# prototype.net
KiCad netlist of a schematic drawn in EAGLE
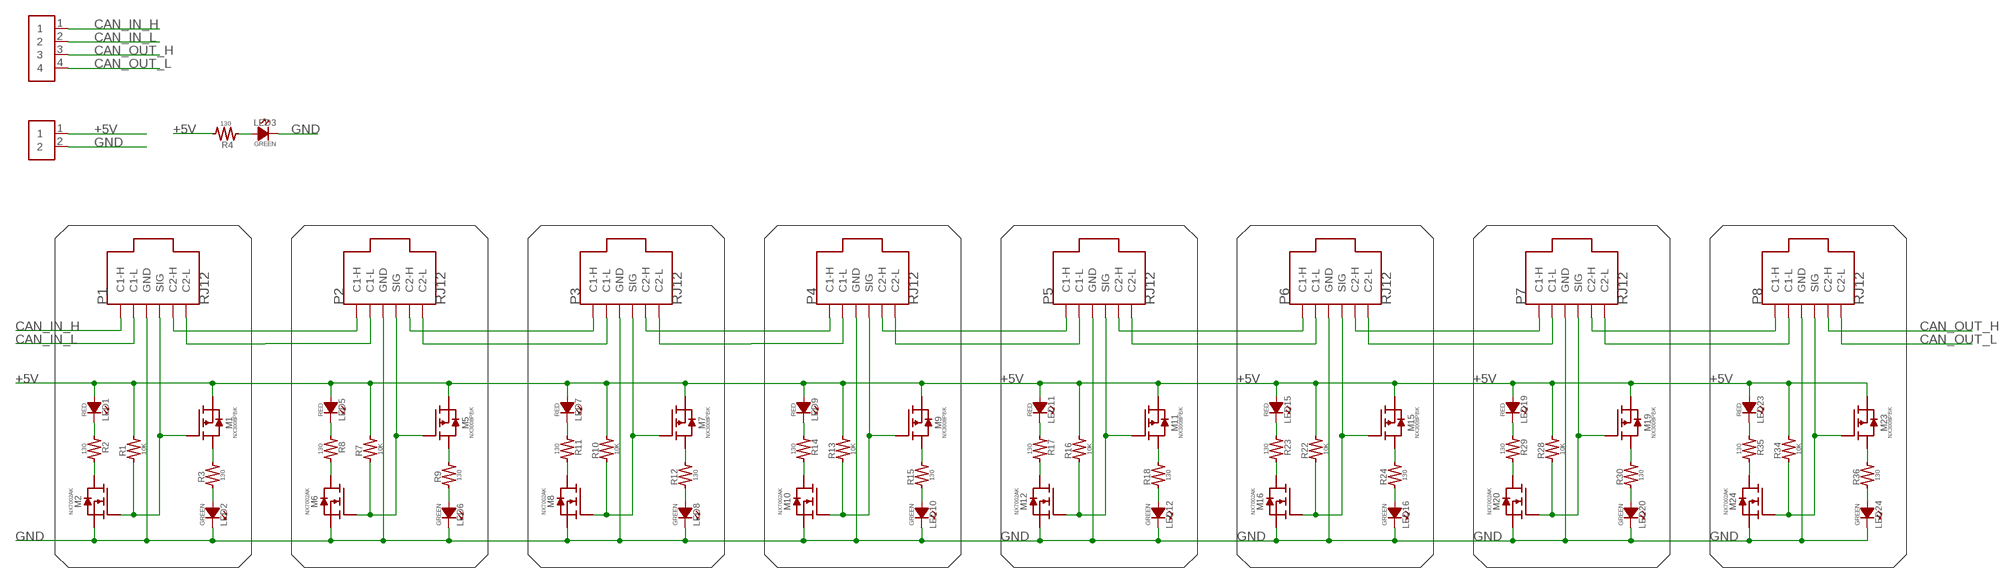
[diagram p0: schematic, sheet 1]

(export (version "E")
  (design (tool "Eeschema 10.0.6"))
  (components
    (comp (ref "LED1")
      (value "RED")
      (footprint "eagle-import:0603-LED")
      (libsource (lib "eagle-import") (part "150060RS75000"))
    )
    (comp (ref "LED2")
      (value "GREEN")
      (footprint "eagle-import:0603-LED")
      (libsource (lib "eagle-import") (part "150060VS75000"))
    )
    (comp (ref "LED3")
      (value "GREEN")
      (footprint "eagle-import:0603-LED")
      (libsource (lib "eagle-import") (part "150060VS75000"))
    )
    (comp (ref "LED5")
      (value "RED")
      (footprint "eagle-import:0603-LED")
      (libsource (lib "eagle-import") (part "150060RS75000"))
    )
    (comp (ref "LED6")
      (value "GREEN")
      (footprint "eagle-import:0603-LED")
      (libsource (lib "eagle-import") (part "150060VS75000"))
    )
    (comp (ref "LED7")
      (value "RED")
      (footprint "eagle-import:0603-LED")
      (libsource (lib "eagle-import") (part "150060RS75000"))
    )
    (comp (ref "LED8")
      (value "GREEN")
      (footprint "eagle-import:0603-LED")
      (libsource (lib "eagle-import") (part "150060VS75000"))
    )
    (comp (ref "LED9")
      (value "RED")
      (footprint "eagle-import:0603-LED")
      (libsource (lib "eagle-import") (part "150060RS75000"))
    )
    (comp (ref "LED10")
      (value "GREEN")
      (footprint "eagle-import:0603-LED")
      (libsource (lib "eagle-import") (part "150060VS75000"))
    )
    (comp (ref "LED11")
      (value "RED")
      (footprint "eagle-import:0603-LED")
      (libsource (lib "eagle-import") (part "150060RS75000"))
    )
    (comp (ref "LED12")
      (value "GREEN")
      (footprint "eagle-import:0603-LED")
      (libsource (lib "eagle-import") (part "150060VS75000"))
    )
    (comp (ref "LED15")
      (value "RED")
      (footprint "eagle-import:0603-LED")
      (libsource (lib "eagle-import") (part "150060RS75000"))
    )
    (comp (ref "LED16")
      (value "GREEN")
      (footprint "eagle-import:0603-LED")
      (libsource (lib "eagle-import") (part "150060VS75000"))
    )
    (comp (ref "LED19")
      (value "RED")
      (footprint "eagle-import:0603-LED")
      (libsource (lib "eagle-import") (part "150060RS75000"))
    )
    (comp (ref "LED20")
      (value "GREEN")
      (footprint "eagle-import:0603-LED")
      (libsource (lib "eagle-import") (part "150060VS75000"))
    )
    (comp (ref "LED23")
      (value "RED")
      (footprint "eagle-import:0603-LED")
      (libsource (lib "eagle-import") (part "150060RS75000"))
    )
    (comp (ref "LED24")
      (value "GREEN")
      (footprint "eagle-import:0603-LED")
      (libsource (lib "eagle-import") (part "150060VS75000"))
    )
    (comp (ref "M1")
      (value "NX3008PBK")
      (footprint "eagle-import:SOT23")
      (libsource (lib "eagle-import") (part "NX3008PBK"))
    )
    (comp (ref "M2")
      (value "NX7002AK")
      (footprint "eagle-import:SOT23")
      (libsource (lib "eagle-import") (part "NX7002AK"))
    )
    (comp (ref "M5")
      (value "NX3008PBK")
      (footprint "eagle-import:SOT23")
      (libsource (lib "eagle-import") (part "NX3008PBK"))
    )
    (comp (ref "M6")
      (value "NX7002AK")
      (footprint "eagle-import:SOT23")
      (libsource (lib "eagle-import") (part "NX7002AK"))
    )
    (comp (ref "M7")
      (value "NX3008PBK")
      (footprint "eagle-import:SOT23")
      (libsource (lib "eagle-import") (part "NX3008PBK"))
    )
    (comp (ref "M8")
      (value "NX7002AK")
      (footprint "eagle-import:SOT23")
      (libsource (lib "eagle-import") (part "NX7002AK"))
    )
    (comp (ref "M9")
      (value "NX3008PBK")
      (footprint "eagle-import:SOT23")
      (libsource (lib "eagle-import") (part "NX3008PBK"))
    )
    (comp (ref "M10")
      (value "NX7002AK")
      (footprint "eagle-import:SOT23")
      (libsource (lib "eagle-import") (part "NX7002AK"))
    )
    (comp (ref "M11")
      (value "NX3008PBK")
      (footprint "eagle-import:SOT23")
      (libsource (lib "eagle-import") (part "NX3008PBK"))
    )
    (comp (ref "M12")
      (value "NX7002AK")
      (footprint "eagle-import:SOT23")
      (libsource (lib "eagle-import") (part "NX7002AK"))
    )
    (comp (ref "M15")
      (value "NX3008PBK")
      (footprint "eagle-import:SOT23")
      (libsource (lib "eagle-import") (part "NX3008PBK"))
    )
    (comp (ref "M16")
      (value "NX7002AK")
      (footprint "eagle-import:SOT23")
      (libsource (lib "eagle-import") (part "NX7002AK"))
    )
    (comp (ref "M19")
      (value "NX3008PBK")
      (footprint "eagle-import:SOT23")
      (libsource (lib "eagle-import") (part "NX3008PBK"))
    )
    (comp (ref "M20")
      (value "NX7002AK")
      (footprint "eagle-import:SOT23")
      (libsource (lib "eagle-import") (part "NX7002AK"))
    )
    (comp (ref "M23")
      (value "NX3008PBK")
      (footprint "eagle-import:SOT23")
      (libsource (lib "eagle-import") (part "NX3008PBK"))
    )
    (comp (ref "M24")
      (value "NX7002AK")
      (footprint "eagle-import:SOT23")
      (libsource (lib "eagle-import") (part "NX7002AK"))
    )
    (comp (ref "P1")
      (value "RJ12")
      (footprint "eagle-import:RJ12")
      (libsource (lib "eagle-import") (part "RJ12"))
    )
    (comp (ref "P2")
      (value "RJ12")
      (footprint "eagle-import:RJ12")
      (libsource (lib "eagle-import") (part "RJ12"))
    )
    (comp (ref "P3")
      (value "RJ12")
      (footprint "eagle-import:RJ12")
      (libsource (lib "eagle-import") (part "RJ12"))
    )
    (comp (ref "P4")
      (value "RJ12")
      (footprint "eagle-import:RJ12")
      (libsource (lib "eagle-import") (part "RJ12"))
    )
    (comp (ref "P5")
      (value "RJ12")
      (footprint "eagle-import:RJ12")
      (libsource (lib "eagle-import") (part "RJ12"))
    )
    (comp (ref "P6")
      (value "RJ12")
      (footprint "eagle-import:RJ12")
      (libsource (lib "eagle-import") (part "RJ12"))
    )
    (comp (ref "P7")
      (value "RJ12")
      (footprint "eagle-import:RJ12")
      (libsource (lib "eagle-import") (part "RJ12"))
    )
    (comp (ref "P8")
      (value "RJ12")
      (footprint "eagle-import:RJ12")
      (libsource (lib "eagle-import") (part "RJ12"))
    )
    (comp (ref "R1")
      (value "10K")
      (footprint "eagle-import:0402")
      (libsource (lib "eagle-import") (part "10K0402"))
    )
    (comp (ref "R2")
      (value "130")
      (footprint "eagle-import:0402")
      (libsource (lib "eagle-import") (part "1300402"))
    )
    (comp (ref "R3")
      (value "130")
      (footprint "eagle-import:0402")
      (libsource (lib "eagle-import") (part "1300402"))
    )
    (comp (ref "R4")
      (value "130")
      (footprint "eagle-import:0402")
      (libsource (lib "eagle-import") (part "1300402"))
    )
    (comp (ref "R7")
      (value "10K")
      (footprint "eagle-import:0402")
      (libsource (lib "eagle-import") (part "10K0402"))
    )
    (comp (ref "R8")
      (value "130")
      (footprint "eagle-import:0402")
      (libsource (lib "eagle-import") (part "1300402"))
    )
    (comp (ref "R9")
      (value "130")
      (footprint "eagle-import:0402")
      (libsource (lib "eagle-import") (part "1300402"))
    )
    (comp (ref "R10")
      (value "10K")
      (footprint "eagle-import:0402")
      (libsource (lib "eagle-import") (part "10K0402"))
    )
    (comp (ref "R11")
      (value "130")
      (footprint "eagle-import:0402")
      (libsource (lib "eagle-import") (part "1300402"))
    )
    (comp (ref "R12")
      (value "130")
      (footprint "eagle-import:0402")
      (libsource (lib "eagle-import") (part "1300402"))
    )
    (comp (ref "R13")
      (value "10K")
      (footprint "eagle-import:0402")
      (libsource (lib "eagle-import") (part "10K0402"))
    )
    (comp (ref "R14")
      (value "130")
      (footprint "eagle-import:0402")
      (libsource (lib "eagle-import") (part "1300402"))
    )
    (comp (ref "R15")
      (value "130")
      (footprint "eagle-import:0402")
      (libsource (lib "eagle-import") (part "1300402"))
    )
    (comp (ref "R16")
      (value "10K")
      (footprint "eagle-import:0402")
      (libsource (lib "eagle-import") (part "10K0402"))
    )
    (comp (ref "R17")
      (value "130")
      (footprint "eagle-import:0402")
      (libsource (lib "eagle-import") (part "1300402"))
    )
    (comp (ref "R18")
      (value "130")
      (footprint "eagle-import:0402")
      (libsource (lib "eagle-import") (part "1300402"))
    )
    (comp (ref "R22")
      (value "10K")
      (footprint "eagle-import:0402")
      (libsource (lib "eagle-import") (part "10K0402"))
    )
    (comp (ref "R23")
      (value "130")
      (footprint "eagle-import:0402")
      (libsource (lib "eagle-import") (part "1300402"))
    )
    (comp (ref "R24")
      (value "130")
      (footprint "eagle-import:0402")
      (libsource (lib "eagle-import") (part "1300402"))
    )
    (comp (ref "R28")
      (value "10K")
      (footprint "eagle-import:0402")
      (libsource (lib "eagle-import") (part "10K0402"))
    )
    (comp (ref "R29")
      (value "130")
      (footprint "eagle-import:0402")
      (libsource (lib "eagle-import") (part "1300402"))
    )
    (comp (ref "R30")
      (value "130")
      (footprint "eagle-import:0402")
      (libsource (lib "eagle-import") (part "1300402"))
    )
    (comp (ref "R34")
      (value "10K")
      (footprint "eagle-import:0402")
      (libsource (lib "eagle-import") (part "10K0402"))
    )
    (comp (ref "R35")
      (value "130")
      (footprint "eagle-import:0402")
      (libsource (lib "eagle-import") (part "1300402"))
    )
    (comp (ref "R36")
      (value "130")
      (footprint "eagle-import:0402")
      (libsource (lib "eagle-import") (part "1300402"))
    )
    (comp (ref "U$1")
      (value "TERMINAL_BLOCK")
      (footprint "eagle-import:TERMINALBLOCK-4")
      (libsource (lib "eagle-import") (part "TERMINAL_BLOCK"))
    )
    (comp (ref "U$2")
      (value "POWER_BLOCK")
      (footprint "eagle-import:TERMINALBLOCK-2")
      (libsource (lib "eagle-import") (part "POWER_BLOCK"))
    )
  )
  (nets
    (net (code "1") (name "/+5V") (class "Default")
      (node (ref "LED1") (pin "2") (pinfunction "+_2") (pintype "bidirectional"))
      (node (ref "LED11") (pin "2") (pinfunction "+_2") (pintype "bidirectional"))
      (node (ref "LED15") (pin "2") (pinfunction "+_2") (pintype "bidirectional"))
      (node (ref "LED19") (pin "2") (pinfunction "+_2") (pintype "bidirectional"))
      (node (ref "LED23") (pin "2") (pinfunction "+_2") (pintype "bidirectional"))
      (node (ref "LED5") (pin "2") (pinfunction "+_2") (pintype "bidirectional"))
      (node (ref "LED7") (pin "2") (pinfunction "+_2") (pintype "bidirectional"))
      (node (ref "LED9") (pin "2") (pinfunction "+_2") (pintype "bidirectional"))
      (node (ref "M1") (pin "2") (pinfunction "SOURCE_2") (pintype "bidirectional"))
      (node (ref "M11") (pin "2") (pinfunction "SOURCE_2") (pintype "bidirectional"))
      (node (ref "M15") (pin "2") (pinfunction "SOURCE_2") (pintype "bidirectional"))
      (node (ref "M19") (pin "2") (pinfunction "SOURCE_2") (pintype "bidirectional"))
      (node (ref "M23") (pin "2") (pinfunction "SOURCE_2") (pintype "bidirectional"))
      (node (ref "M5") (pin "2") (pinfunction "SOURCE_2") (pintype "bidirectional"))
      (node (ref "M7") (pin "2") (pinfunction "SOURCE_2") (pintype "bidirectional"))
      (node (ref "M9") (pin "2") (pinfunction "SOURCE_2") (pintype "bidirectional"))
      (node (ref "R1") (pin "2") (pinfunction "2_2") (pintype "bidirectional"))
      (node (ref "R10") (pin "2") (pinfunction "2_2") (pintype "bidirectional"))
      (node (ref "R13") (pin "2") (pinfunction "2_2") (pintype "bidirectional"))
      (node (ref "R16") (pin "2") (pinfunction "2_2") (pintype "bidirectional"))
      (node (ref "R22") (pin "2") (pinfunction "2_2") (pintype "bidirectional"))
      (node (ref "R28") (pin "2") (pinfunction "2_2") (pintype "bidirectional"))
      (node (ref "R34") (pin "2") (pinfunction "2_2") (pintype "bidirectional"))
      (node (ref "R4") (pin "2") (pinfunction "2_2") (pintype "bidirectional"))
      (node (ref "R7") (pin "2") (pinfunction "2_2") (pintype "bidirectional"))
      (node (ref "U$2") (pin "1") (pinfunction "1_1") (pintype "bidirectional"))
    )
    (net (code "2") (name "/CAN_IN_H") (class "Default")
      (node (ref "P1") (pin "1") (pinfunction "C1-H_1") (pintype "bidirectional"))
      (node (ref "U$1") (pin "1") (pinfunction "1_1") (pintype "bidirectional"))
    )
    (net (code "3") (name "/CAN_IN_L") (class "Default")
      (node (ref "P1") (pin "2") (pinfunction "C1-L_2") (pintype "bidirectional"))
      (node (ref "U$1") (pin "2") (pinfunction "2_2") (pintype "bidirectional"))
    )
    (net (code "4") (name "/CAN_OUT_H") (class "Default")
      (node (ref "P8") (pin "5") (pinfunction "C2-H_5") (pintype "bidirectional"))
      (node (ref "U$1") (pin "3") (pinfunction "3_3") (pintype "bidirectional"))
    )
    (net (code "5") (name "/CAN_OUT_L") (class "Default")
      (node (ref "P8") (pin "6") (pinfunction "C2-L_6") (pintype "bidirectional"))
      (node (ref "U$1") (pin "4") (pinfunction "4_4") (pintype "bidirectional"))
    )
    (net (code "6") (name "/GND") (class "Default")
      (node (ref "LED10") (pin "1") (pinfunction "-_1") (pintype "bidirectional"))
      (node (ref "LED12") (pin "1") (pinfunction "-_1") (pintype "bidirectional"))
      (node (ref "LED16") (pin "1") (pinfunction "-_1") (pintype "bidirectional"))
      (node (ref "LED2") (pin "1") (pinfunction "-_1") (pintype "bidirectional"))
      (node (ref "LED20") (pin "1") (pinfunction "-_1") (pintype "bidirectional"))
      (node (ref "LED24") (pin "1") (pinfunction "-_1") (pintype "bidirectional"))
      (node (ref "LED3") (pin "1") (pinfunction "-_1") (pintype "bidirectional"))
      (node (ref "LED6") (pin "1") (pinfunction "-_1") (pintype "bidirectional"))
      (node (ref "LED8") (pin "1") (pinfunction "-_1") (pintype "bidirectional"))
      (node (ref "M10") (pin "2") (pinfunction "SOURCE_2") (pintype "bidirectional"))
      (node (ref "M12") (pin "2") (pinfunction "SOURCE_2") (pintype "bidirectional"))
      (node (ref "M16") (pin "2") (pinfunction "SOURCE_2") (pintype "bidirectional"))
      (node (ref "M2") (pin "2") (pinfunction "SOURCE_2") (pintype "bidirectional"))
      (node (ref "M20") (pin "2") (pinfunction "SOURCE_2") (pintype "bidirectional"))
      (node (ref "M24") (pin "2") (pinfunction "SOURCE_2") (pintype "bidirectional"))
      (node (ref "M6") (pin "2") (pinfunction "SOURCE_2") (pintype "bidirectional"))
      (node (ref "M8") (pin "2") (pinfunction "SOURCE_2") (pintype "bidirectional"))
      (node (ref "P1") (pin "3") (pinfunction "GND_3") (pintype "bidirectional"))
      (node (ref "P2") (pin "3") (pinfunction "GND_3") (pintype "bidirectional"))
      (node (ref "P3") (pin "3") (pinfunction "GND_3") (pintype "bidirectional"))
      (node (ref "P4") (pin "3") (pinfunction "GND_3") (pintype "bidirectional"))
      (node (ref "P5") (pin "3") (pinfunction "GND_3") (pintype "bidirectional"))
      (node (ref "P6") (pin "3") (pinfunction "GND_3") (pintype "bidirectional"))
      (node (ref "P7") (pin "3") (pinfunction "GND_3") (pintype "bidirectional"))
      (node (ref "P8") (pin "3") (pinfunction "GND_3") (pintype "bidirectional"))
      (node (ref "U$2") (pin "2") (pinfunction "2_2") (pintype "bidirectional"))
    )
    (net (code "7") (name "Net-(LED1--)") (class "Default")
      (node (ref "LED1") (pin "1") (pinfunction "-_1") (pintype "bidirectional"))
      (node (ref "R2") (pin "1") (pinfunction "1_1") (pintype "bidirectional"))
    )
    (net (code "8") (name "Net-(LED2-+)") (class "Default")
      (node (ref "LED2") (pin "2") (pinfunction "+_2") (pintype "bidirectional"))
      (node (ref "R3") (pin "1") (pinfunction "1_1") (pintype "bidirectional"))
    )
    (net (code "9") (name "Net-(LED3-+)") (class "Default")
      (node (ref "LED3") (pin "2") (pinfunction "+_2") (pintype "bidirectional"))
      (node (ref "R4") (pin "1") (pinfunction "1_1") (pintype "bidirectional"))
    )
    (net (code "10") (name "Net-(LED5--)") (class "Default")
      (node (ref "LED5") (pin "1") (pinfunction "-_1") (pintype "bidirectional"))
      (node (ref "R8") (pin "1") (pinfunction "1_1") (pintype "bidirectional"))
    )
    (net (code "11") (name "Net-(LED6-+)") (class "Default")
      (node (ref "LED6") (pin "2") (pinfunction "+_2") (pintype "bidirectional"))
      (node (ref "R9") (pin "1") (pinfunction "1_1") (pintype "bidirectional"))
    )
    (net (code "12") (name "Net-(LED7--)") (class "Default")
      (node (ref "LED7") (pin "1") (pinfunction "-_1") (pintype "bidirectional"))
      (node (ref "R11") (pin "1") (pinfunction "1_1") (pintype "bidirectional"))
    )
    (net (code "13") (name "Net-(LED8-+)") (class "Default")
      (node (ref "LED8") (pin "2") (pinfunction "+_2") (pintype "bidirectional"))
      (node (ref "R12") (pin "1") (pinfunction "1_1") (pintype "bidirectional"))
    )
    (net (code "14") (name "Net-(LED9--)") (class "Default")
      (node (ref "LED9") (pin "1") (pinfunction "-_1") (pintype "bidirectional"))
      (node (ref "R14") (pin "1") (pinfunction "1_1") (pintype "bidirectional"))
    )
    (net (code "15") (name "Net-(LED10-+)") (class "Default")
      (node (ref "LED10") (pin "2") (pinfunction "+_2") (pintype "bidirectional"))
      (node (ref "R15") (pin "1") (pinfunction "1_1") (pintype "bidirectional"))
    )
    (net (code "16") (name "Net-(LED11--)") (class "Default")
      (node (ref "LED11") (pin "1") (pinfunction "-_1") (pintype "bidirectional"))
      (node (ref "R17") (pin "1") (pinfunction "1_1") (pintype "bidirectional"))
    )
    (net (code "17") (name "Net-(LED12-+)") (class "Default")
      (node (ref "LED12") (pin "2") (pinfunction "+_2") (pintype "bidirectional"))
      (node (ref "R18") (pin "1") (pinfunction "1_1") (pintype "bidirectional"))
    )
    (net (code "18") (name "Net-(LED15--)") (class "Default")
      (node (ref "LED15") (pin "1") (pinfunction "-_1") (pintype "bidirectional"))
      (node (ref "R23") (pin "1") (pinfunction "1_1") (pintype "bidirectional"))
    )
    (net (code "19") (name "Net-(LED16-+)") (class "Default")
      (node (ref "LED16") (pin "2") (pinfunction "+_2") (pintype "bidirectional"))
      (node (ref "R24") (pin "1") (pinfunction "1_1") (pintype "bidirectional"))
    )
    (net (code "20") (name "Net-(LED19--)") (class "Default")
      (node (ref "LED19") (pin "1") (pinfunction "-_1") (pintype "bidirectional"))
      (node (ref "R29") (pin "1") (pinfunction "1_1") (pintype "bidirectional"))
    )
    (net (code "21") (name "Net-(LED20-+)") (class "Default")
      (node (ref "LED20") (pin "2") (pinfunction "+_2") (pintype "bidirectional"))
      (node (ref "R30") (pin "1") (pinfunction "1_1") (pintype "bidirectional"))
    )
    (net (code "22") (name "Net-(LED23--)") (class "Default")
      (node (ref "LED23") (pin "1") (pinfunction "-_1") (pintype "bidirectional"))
      (node (ref "R35") (pin "1") (pinfunction "1_1") (pintype "bidirectional"))
    )
    (net (code "23") (name "Net-(LED24-+)") (class "Default")
      (node (ref "LED24") (pin "2") (pinfunction "+_2") (pintype "bidirectional"))
      (node (ref "R36") (pin "1") (pinfunction "1_1") (pintype "bidirectional"))
    )
    (net (code "24") (name "Net-(M1-DRAIN)") (class "Default")
      (node (ref "M1") (pin "3") (pinfunction "DRAIN_3") (pintype "bidirectional"))
      (node (ref "R3") (pin "2") (pinfunction "2_2") (pintype "bidirectional"))
    )
    (net (code "25") (name "Net-(M1-GATE)") (class "Default")
      (node (ref "M1") (pin "1") (pinfunction "GATE_1") (pintype "bidirectional"))
      (node (ref "M2") (pin "1") (pinfunction "GATE_1") (pintype "bidirectional"))
      (node (ref "P1") (pin "4") (pinfunction "SIG_4") (pintype "bidirectional"))
      (node (ref "R1") (pin "1") (pinfunction "1_1") (pintype "bidirectional"))
    )
    (net (code "26") (name "Net-(M2-DRAIN)") (class "Default")
      (node (ref "M2") (pin "3") (pinfunction "DRAIN_3") (pintype "bidirectional"))
      (node (ref "R2") (pin "2") (pinfunction "2_2") (pintype "bidirectional"))
    )
    (net (code "27") (name "Net-(M5-DRAIN)") (class "Default")
      (node (ref "M5") (pin "3") (pinfunction "DRAIN_3") (pintype "bidirectional"))
      (node (ref "R9") (pin "2") (pinfunction "2_2") (pintype "bidirectional"))
    )
    (net (code "28") (name "Net-(M5-GATE)") (class "Default")
      (node (ref "M5") (pin "1") (pinfunction "GATE_1") (pintype "bidirectional"))
      (node (ref "M6") (pin "1") (pinfunction "GATE_1") (pintype "bidirectional"))
      (node (ref "P2") (pin "4") (pinfunction "SIG_4") (pintype "bidirectional"))
      (node (ref "R7") (pin "1") (pinfunction "1_1") (pintype "bidirectional"))
    )
    (net (code "29") (name "Net-(M6-DRAIN)") (class "Default")
      (node (ref "M6") (pin "3") (pinfunction "DRAIN_3") (pintype "bidirectional"))
      (node (ref "R8") (pin "2") (pinfunction "2_2") (pintype "bidirectional"))
    )
    (net (code "30") (name "Net-(M7-DRAIN)") (class "Default")
      (node (ref "M7") (pin "3") (pinfunction "DRAIN_3") (pintype "bidirectional"))
      (node (ref "R12") (pin "2") (pinfunction "2_2") (pintype "bidirectional"))
    )
    (net (code "31") (name "Net-(M7-GATE)") (class "Default")
      (node (ref "M7") (pin "1") (pinfunction "GATE_1") (pintype "bidirectional"))
      (node (ref "M8") (pin "1") (pinfunction "GATE_1") (pintype "bidirectional"))
      (node (ref "P3") (pin "4") (pinfunction "SIG_4") (pintype "bidirectional"))
      (node (ref "R10") (pin "1") (pinfunction "1_1") (pintype "bidirectional"))
    )
    (net (code "32") (name "Net-(M8-DRAIN)") (class "Default")
      (node (ref "M8") (pin "3") (pinfunction "DRAIN_3") (pintype "bidirectional"))
      (node (ref "R11") (pin "2") (pinfunction "2_2") (pintype "bidirectional"))
    )
    (net (code "33") (name "Net-(M9-DRAIN)") (class "Default")
      (node (ref "M9") (pin "3") (pinfunction "DRAIN_3") (pintype "bidirectional"))
      (node (ref "R15") (pin "2") (pinfunction "2_2") (pintype "bidirectional"))
    )
    (net (code "34") (name "Net-(M10-DRAIN)") (class "Default")
      (node (ref "M10") (pin "3") (pinfunction "DRAIN_3") (pintype "bidirectional"))
      (node (ref "R14") (pin "2") (pinfunction "2_2") (pintype "bidirectional"))
    )
    (net (code "35") (name "Net-(M10-GATE)") (class "Default")
      (node (ref "M10") (pin "1") (pinfunction "GATE_1") (pintype "bidirectional"))
      (node (ref "M9") (pin "1") (pinfunction "GATE_1") (pintype "bidirectional"))
      (node (ref "P4") (pin "4") (pinfunction "SIG_4") (pintype "bidirectional"))
      (node (ref "R13") (pin "1") (pinfunction "1_1") (pintype "bidirectional"))
    )
    (net (code "36") (name "Net-(M11-DRAIN)") (class "Default")
      (node (ref "M11") (pin "3") (pinfunction "DRAIN_3") (pintype "bidirectional"))
      (node (ref "R18") (pin "2") (pinfunction "2_2") (pintype "bidirectional"))
    )
    (net (code "37") (name "Net-(M11-GATE)") (class "Default")
      (node (ref "M11") (pin "1") (pinfunction "GATE_1") (pintype "bidirectional"))
      (node (ref "M12") (pin "1") (pinfunction "GATE_1") (pintype "bidirectional"))
      (node (ref "P5") (pin "4") (pinfunction "SIG_4") (pintype "bidirectional"))
      (node (ref "R16") (pin "1") (pinfunction "1_1") (pintype "bidirectional"))
    )
    (net (code "38") (name "Net-(M12-DRAIN)") (class "Default")
      (node (ref "M12") (pin "3") (pinfunction "DRAIN_3") (pintype "bidirectional"))
      (node (ref "R17") (pin "2") (pinfunction "2_2") (pintype "bidirectional"))
    )
    (net (code "39") (name "Net-(M15-DRAIN)") (class "Default")
      (node (ref "M15") (pin "3") (pinfunction "DRAIN_3") (pintype "bidirectional"))
      (node (ref "R24") (pin "2") (pinfunction "2_2") (pintype "bidirectional"))
    )
    (net (code "40") (name "Net-(M15-GATE)") (class "Default")
      (node (ref "M15") (pin "1") (pinfunction "GATE_1") (pintype "bidirectional"))
      (node (ref "M16") (pin "1") (pinfunction "GATE_1") (pintype "bidirectional"))
      (node (ref "P6") (pin "4") (pinfunction "SIG_4") (pintype "bidirectional"))
      (node (ref "R22") (pin "1") (pinfunction "1_1") (pintype "bidirectional"))
    )
    (net (code "41") (name "Net-(M16-DRAIN)") (class "Default")
      (node (ref "M16") (pin "3") (pinfunction "DRAIN_3") (pintype "bidirectional"))
      (node (ref "R23") (pin "2") (pinfunction "2_2") (pintype "bidirectional"))
    )
    (net (code "42") (name "Net-(M19-DRAIN)") (class "Default")
      (node (ref "M19") (pin "3") (pinfunction "DRAIN_3") (pintype "bidirectional"))
      (node (ref "R30") (pin "2") (pinfunction "2_2") (pintype "bidirectional"))
    )
    (net (code "43") (name "Net-(M19-GATE)") (class "Default")
      (node (ref "M19") (pin "1") (pinfunction "GATE_1") (pintype "bidirectional"))
      (node (ref "M20") (pin "1") (pinfunction "GATE_1") (pintype "bidirectional"))
      (node (ref "P7") (pin "4") (pinfunction "SIG_4") (pintype "bidirectional"))
      (node (ref "R28") (pin "1") (pinfunction "1_1") (pintype "bidirectional"))
    )
    (net (code "44") (name "Net-(M20-DRAIN)") (class "Default")
      (node (ref "M20") (pin "3") (pinfunction "DRAIN_3") (pintype "bidirectional"))
      (node (ref "R29") (pin "2") (pinfunction "2_2") (pintype "bidirectional"))
    )
    (net (code "45") (name "Net-(M23-DRAIN)") (class "Default")
      (node (ref "M23") (pin "3") (pinfunction "DRAIN_3") (pintype "bidirectional"))
      (node (ref "R36") (pin "2") (pinfunction "2_2") (pintype "bidirectional"))
    )
    (net (code "46") (name "Net-(M23-GATE)") (class "Default")
      (node (ref "M23") (pin "1") (pinfunction "GATE_1") (pintype "bidirectional"))
      (node (ref "M24") (pin "1") (pinfunction "GATE_1") (pintype "bidirectional"))
      (node (ref "P8") (pin "4") (pinfunction "SIG_4") (pintype "bidirectional"))
      (node (ref "R34") (pin "1") (pinfunction "1_1") (pintype "bidirectional"))
    )
    (net (code "47") (name "Net-(M24-DRAIN)") (class "Default")
      (node (ref "M24") (pin "3") (pinfunction "DRAIN_3") (pintype "bidirectional"))
      (node (ref "R35") (pin "2") (pinfunction "2_2") (pintype "bidirectional"))
    )
    (net (code "48") (name "Net-(P1-C2-H)") (class "Default")
      (node (ref "P1") (pin "5") (pinfunction "C2-H_5") (pintype "bidirectional"))
      (node (ref "P2") (pin "1") (pinfunction "C1-H_1") (pintype "bidirectional"))
    )
    (net (code "49") (name "Net-(P1-C2-L)") (class "Default")
      (node (ref "P1") (pin "6") (pinfunction "C2-L_6") (pintype "bidirectional"))
      (node (ref "P2") (pin "2") (pinfunction "C1-L_2") (pintype "bidirectional"))
    )
    (net (code "50") (name "Net-(P2-C2-H)") (class "Default")
      (node (ref "P2") (pin "5") (pinfunction "C2-H_5") (pintype "bidirectional"))
      (node (ref "P3") (pin "1") (pinfunction "C1-H_1") (pintype "bidirectional"))
    )
    (net (code "51") (name "Net-(P2-C2-L)") (class "Default")
      (node (ref "P2") (pin "6") (pinfunction "C2-L_6") (pintype "bidirectional"))
      (node (ref "P3") (pin "2") (pinfunction "C1-L_2") (pintype "bidirectional"))
    )
    (net (code "52") (name "Net-(P3-C2-H)") (class "Default")
      (node (ref "P3") (pin "5") (pinfunction "C2-H_5") (pintype "bidirectional"))
      (node (ref "P4") (pin "1") (pinfunction "C1-H_1") (pintype "bidirectional"))
    )
    (net (code "53") (name "Net-(P3-C2-L)") (class "Default")
      (node (ref "P3") (pin "6") (pinfunction "C2-L_6") (pintype "bidirectional"))
      (node (ref "P4") (pin "2") (pinfunction "C1-L_2") (pintype "bidirectional"))
    )
    (net (code "54") (name "Net-(P4-C2-H)") (class "Default")
      (node (ref "P4") (pin "5") (pinfunction "C2-H_5") (pintype "bidirectional"))
      (node (ref "P5") (pin "1") (pinfunction "C1-H_1") (pintype "bidirectional"))
    )
    (net (code "55") (name "Net-(P4-C2-L)") (class "Default")
      (node (ref "P4") (pin "6") (pinfunction "C2-L_6") (pintype "bidirectional"))
      (node (ref "P5") (pin "2") (pinfunction "C1-L_2") (pintype "bidirectional"))
    )
    (net (code "56") (name "Net-(P5-C2-H)") (class "Default")
      (node (ref "P5") (pin "5") (pinfunction "C2-H_5") (pintype "bidirectional"))
      (node (ref "P6") (pin "1") (pinfunction "C1-H_1") (pintype "bidirectional"))
    )
    (net (code "57") (name "Net-(P5-C2-L)") (class "Default")
      (node (ref "P5") (pin "6") (pinfunction "C2-L_6") (pintype "bidirectional"))
      (node (ref "P6") (pin "2") (pinfunction "C1-L_2") (pintype "bidirectional"))
    )
    (net (code "58") (name "Net-(P6-C2-H)") (class "Default")
      (node (ref "P6") (pin "5") (pinfunction "C2-H_5") (pintype "bidirectional"))
      (node (ref "P7") (pin "1") (pinfunction "C1-H_1") (pintype "bidirectional"))
    )
    (net (code "59") (name "Net-(P6-C2-L)") (class "Default")
      (node (ref "P6") (pin "6") (pinfunction "C2-L_6") (pintype "bidirectional"))
      (node (ref "P7") (pin "2") (pinfunction "C1-L_2") (pintype "bidirectional"))
    )
    (net (code "60") (name "Net-(P7-C2-H)") (class "Default")
      (node (ref "P7") (pin "5") (pinfunction "C2-H_5") (pintype "bidirectional"))
      (node (ref "P8") (pin "1") (pinfunction "C1-H_1") (pintype "bidirectional"))
    )
    (net (code "61") (name "Net-(P7-C2-L)") (class "Default")
      (node (ref "P7") (pin "6") (pinfunction "C2-L_6") (pintype "bidirectional"))
      (node (ref "P8") (pin "2") (pinfunction "C1-L_2") (pintype "bidirectional"))
    )
  )
)
